# 12_LMS2_Power.net
KiCad netlist of a schematic drawn in Altium Designer
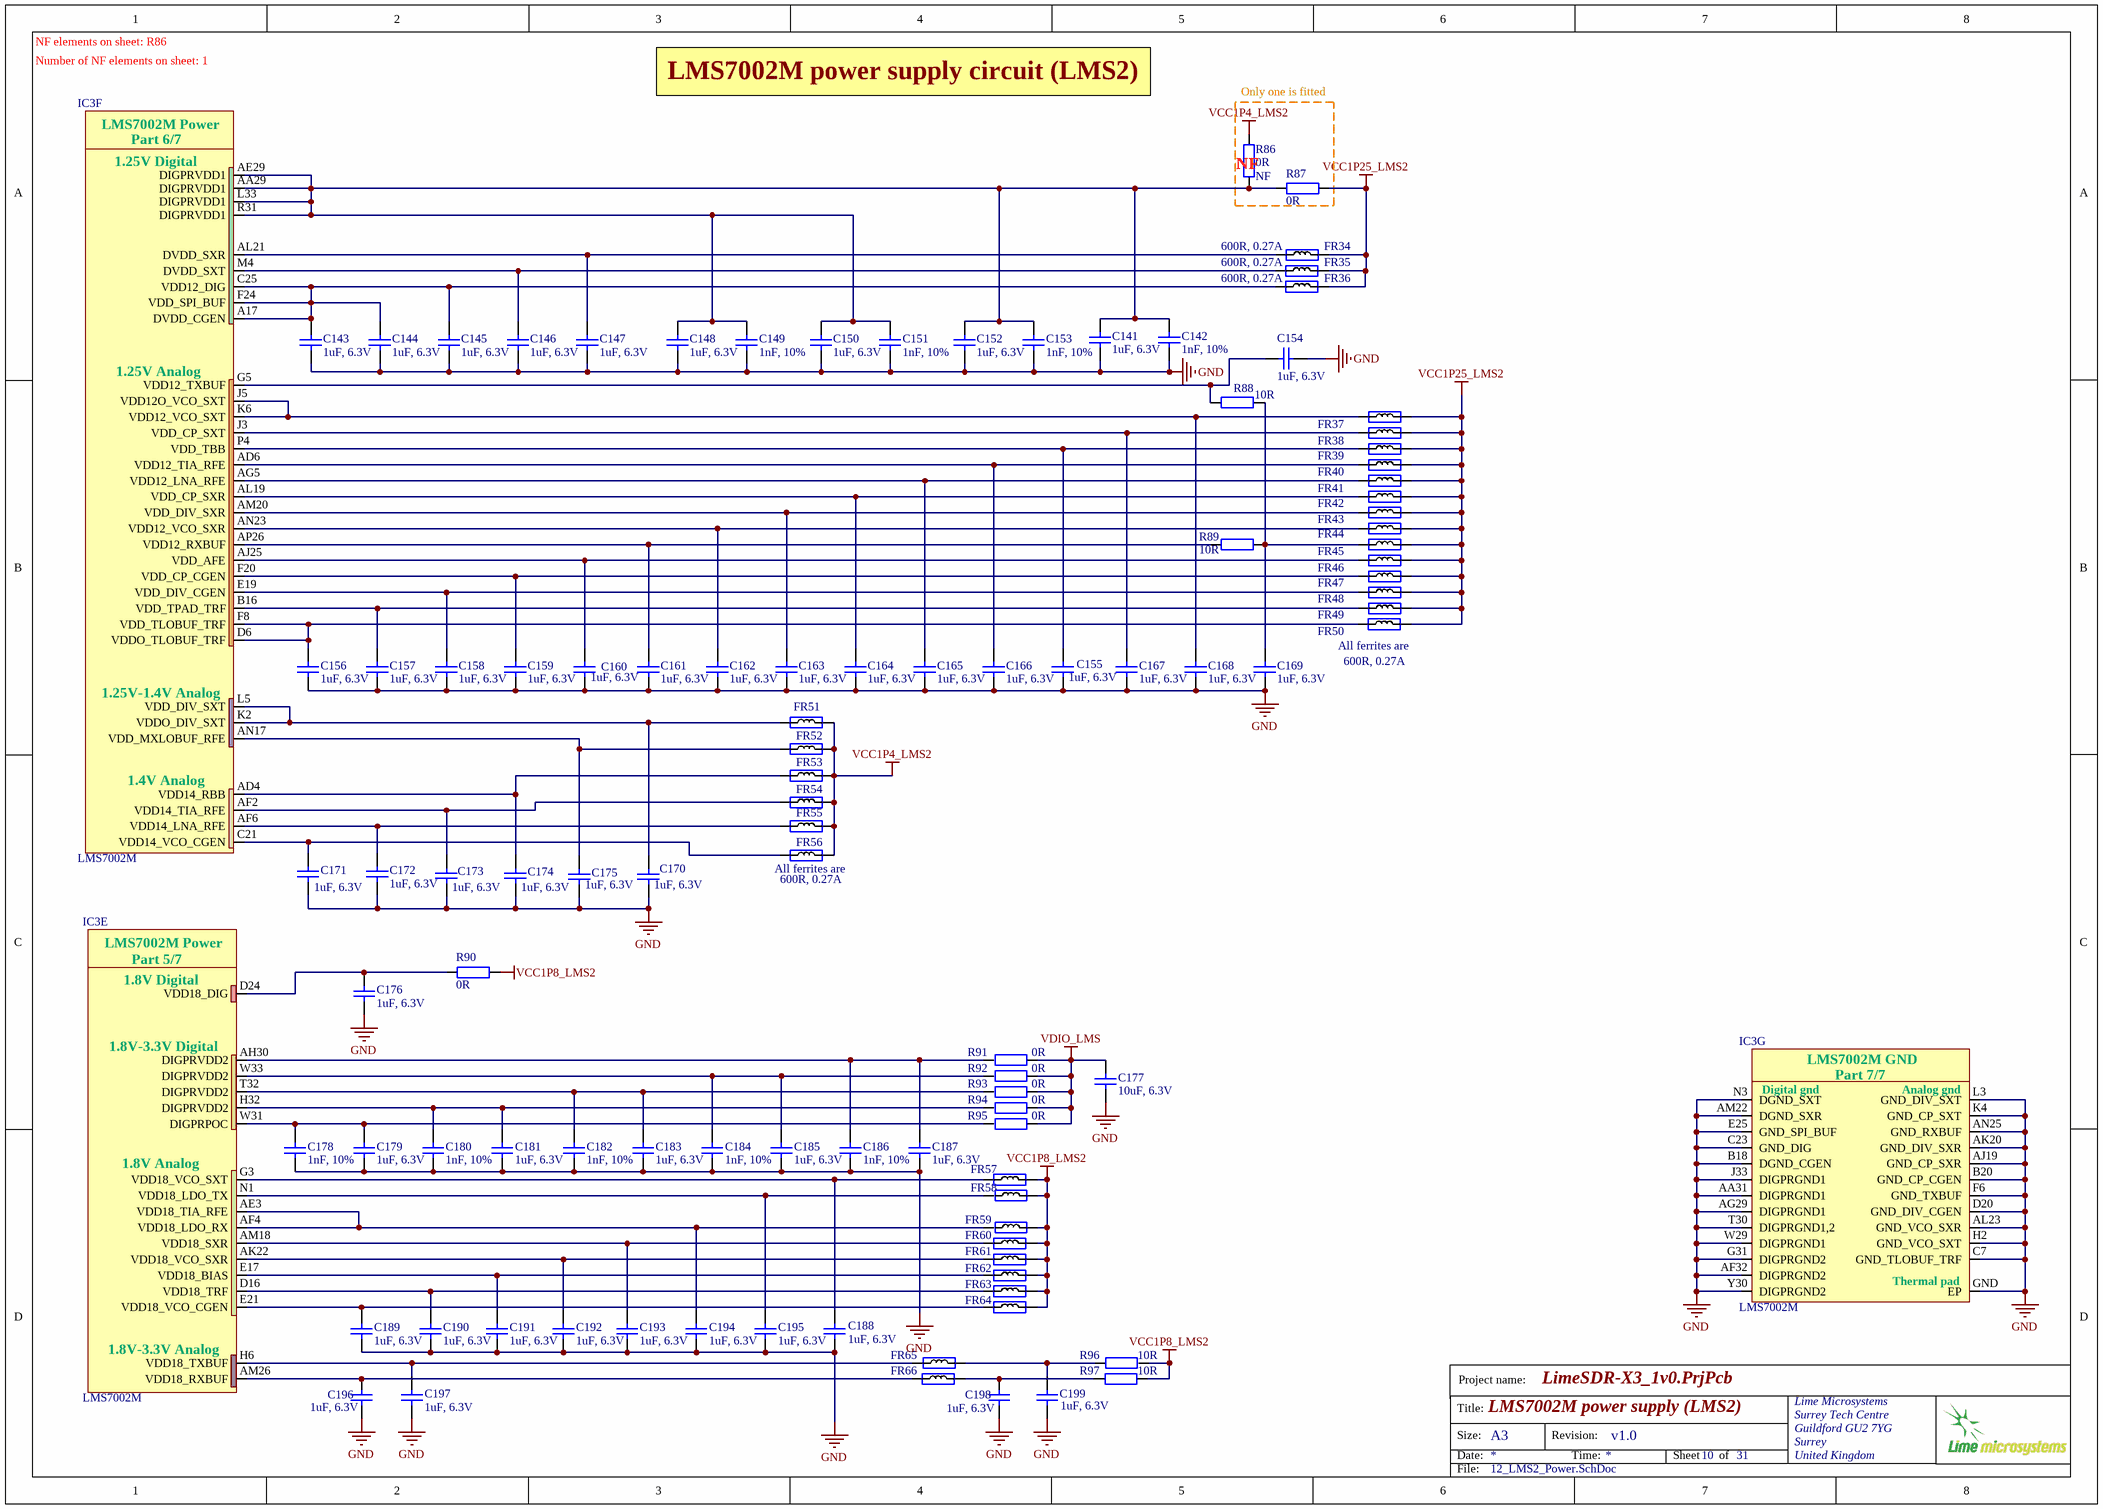
[diagram p0: 12_LMS2_Power.SchDoc]

(export (version "E")
  (design (tool "Eeschema 10.0.6"))
  (components
    (comp (ref "C141")
      (value "1uF, 6.3V")
      (footprint "CAP0201")
      (fields (field (name "TOLERANCE") "±20%") (field (name "MANUFACTURER") "TDK Corporation"))
      (libsource (lib "") (part "Cap_0402_2"))
    )
    (comp (ref "C142")
      (value "1nF, 10%")
      (footprint "CAP0201")
      (fields (field (name "TOLERANCE") "±10%") (field (name "MANUFACTURER") "TDK Corporation"))
      (libsource (lib "") (part "Cap_0402_2"))
    )
    (comp (ref "C143")
      (value "1uF, 6.3V")
      (footprint "CAP0201")
      (fields (field (name "TOLERANCE") "±20%") (field (name "MANUFACTURER") "TDK Corporation"))
      (libsource (lib "") (part "Cap_0402_1"))
    )
    (comp (ref "C144")
      (value "1uF, 6.3V")
      (footprint "CAP0201")
      (fields (field (name "TOLERANCE") "±20%") (field (name "MANUFACTURER") "TDK Corporation"))
      (libsource (lib "") (part "Cap_0402_1"))
    )
    (comp (ref "C145")
      (value "1uF, 6.3V")
      (footprint "CAP0201")
      (fields (field (name "TOLERANCE") "±20%") (field (name "MANUFACTURER") "TDK Corporation"))
      (libsource (lib "") (part "Cap_0402_1"))
    )
    (comp (ref "C146")
      (value "1uF, 6.3V")
      (footprint "CAP0201")
      (fields (field (name "TOLERANCE") "±20%") (field (name "MANUFACTURER") "TDK Corporation"))
      (libsource (lib "") (part "Cap_0402_2"))
    )
    (comp (ref "C147")
      (value "1uF, 6.3V")
      (footprint "CAP0201")
      (fields (field (name "TOLERANCE") "±20%") (field (name "MANUFACTURER") "TDK Corporation"))
      (libsource (lib "") (part "Cap_0402_1"))
    )
    (comp (ref "C148")
      (value "1uF, 6.3V")
      (footprint "CAP0201")
      (fields (field (name "TOLERANCE") "±20%") (field (name "MANUFACTURER") "TDK Corporation"))
      (libsource (lib "") (part "Cap_0402_2"))
    )
    (comp (ref "C149")
      (value "1nF, 10%")
      (footprint "CAP0201")
      (fields (field (name "TOLERANCE") "±10%") (field (name "MANUFACTURER") "TDK Corporation"))
      (libsource (lib "") (part "Cap_0402_2"))
    )
    (comp (ref "C150")
      (value "1uF, 6.3V")
      (footprint "CAP0201")
      (fields (field (name "TOLERANCE") "±20%") (field (name "MANUFACTURER") "TDK Corporation"))
      (libsource (lib "") (part "Cap_0402_2"))
    )
    (comp (ref "C151")
      (value "1nF, 10%")
      (footprint "CAP0201")
      (fields (field (name "TOLERANCE") "±10%") (field (name "MANUFACTURER") "TDK Corporation"))
      (libsource (lib "") (part "Cap_0402_2"))
    )
    (comp (ref "C152")
      (value "1uF, 6.3V")
      (footprint "CAP0201")
      (fields (field (name "TOLERANCE") "±20%") (field (name "MANUFACTURER") "TDK Corporation"))
      (libsource (lib "") (part "Cap_0402_2"))
    )
    (comp (ref "C153")
      (value "1nF, 10%")
      (footprint "CAP0201")
      (fields (field (name "TOLERANCE") "±10%") (field (name "MANUFACTURER") "TDK Corporation"))
      (libsource (lib "") (part "Cap_0402_2"))
    )
    (comp (ref "C154")
      (value "1uF, 6.3V")
      (footprint "CAP0201")
      (fields (field (name "TOLERANCE") "±20%") (field (name "MANUFACTURER") "TDK Corporation"))
      (libsource (lib "") (part "Cap_0402_4"))
    )
    (comp (ref "C155")
      (value "1uF, 6.3V")
      (footprint "CAP0201")
      (fields (field (name "TOLERANCE") "±20%") (field (name "MANUFACTURER") "TDK Corporation"))
      (libsource (lib "") (part "Cap_0402_1"))
    )
    (comp (ref "C156")
      (value "1uF, 6.3V")
      (footprint "CAP0201")
      (fields (field (name "TOLERANCE") "±20%") (field (name "MANUFACTURER") "TDK Corporation"))
      (libsource (lib "") (part "Cap_0402_1"))
    )
    (comp (ref "C157")
      (value "1uF, 6.3V")
      (footprint "CAP0201")
      (fields (field (name "TOLERANCE") "±20%") (field (name "MANUFACTURER") "TDK Corporation"))
      (libsource (lib "") (part "Cap_0402_1"))
    )
    (comp (ref "C158")
      (value "1uF, 6.3V")
      (footprint "CAP0201")
      (fields (field (name "TOLERANCE") "±20%") (field (name "MANUFACTURER") "TDK Corporation"))
      (libsource (lib "") (part "Cap_0402_1"))
    )
    (comp (ref "C159")
      (value "1uF, 6.3V")
      (footprint "CAP0201")
      (fields (field (name "TOLERANCE") "±20%") (field (name "MANUFACTURER") "TDK Corporation"))
      (libsource (lib "") (part "Cap_0402_2"))
    )
    (comp (ref "C160")
      (value "1uF, 6.3V")
      (footprint "CAP0201")
      (fields (field (name "TOLERANCE") "±20%") (field (name "MANUFACTURER") "TDK Corporation"))
      (libsource (lib "") (part "Cap_0402_1"))
    )
    (comp (ref "C161")
      (value "1uF, 6.3V")
      (footprint "CAP0201")
      (fields (field (name "TOLERANCE") "±20%") (field (name "MANUFACTURER") "TDK Corporation"))
      (libsource (lib "") (part "Cap_0402_1"))
    )
    (comp (ref "C162")
      (value "1uF, 6.3V")
      (footprint "CAP0201")
      (fields (field (name "TOLERANCE") "±20%") (field (name "MANUFACTURER") "TDK Corporation"))
      (libsource (lib "") (part "Cap_0402_1"))
    )
    (comp (ref "C163")
      (value "1uF, 6.3V")
      (footprint "CAP0201")
      (fields (field (name "TOLERANCE") "±20%") (field (name "MANUFACTURER") "TDK Corporation"))
      (libsource (lib "") (part "Cap_0402_1"))
    )
    (comp (ref "C164")
      (value "1uF, 6.3V")
      (footprint "CAP0201")
      (fields (field (name "TOLERANCE") "±20%") (field (name "MANUFACTURER") "TDK Corporation"))
      (libsource (lib "") (part "Cap_0402_1"))
    )
    (comp (ref "C165")
      (value "1uF, 6.3V")
      (footprint "CAP0201")
      (fields (field (name "TOLERANCE") "±20%") (field (name "MANUFACTURER") "TDK Corporation"))
      (libsource (lib "") (part "Cap_0402_1"))
    )
    (comp (ref "C166")
      (value "1uF, 6.3V")
      (footprint "CAP0201")
      (fields (field (name "TOLERANCE") "±20%") (field (name "MANUFACTURER") "TDK Corporation"))
      (libsource (lib "") (part "Cap_0402_2"))
    )
    (comp (ref "C167")
      (value "1uF, 6.3V")
      (footprint "CAP0201")
      (fields (field (name "TOLERANCE") "±20%") (field (name "MANUFACTURER") "TDK Corporation"))
      (libsource (lib "") (part "Cap_0402_1"))
    )
    (comp (ref "C168")
      (value "1uF, 6.3V")
      (footprint "CAP0201")
      (fields (field (name "TOLERANCE") "±20%") (field (name "MANUFACTURER") "TDK Corporation"))
      (libsource (lib "") (part "Cap_0402_2"))
    )
    (comp (ref "C169")
      (value "1uF, 6.3V")
      (footprint "CAP0201")
      (fields (field (name "TOLERANCE") "±20%") (field (name "MANUFACTURER") "TDK Corporation"))
      (libsource (lib "") (part "Cap_0402_2"))
    )
    (comp (ref "C170")
      (value "1uF, 6.3V")
      (footprint "CAP0201")
      (fields (field (name "TOLERANCE") "±20%") (field (name "MANUFACTURER") "TDK Corporation"))
      (libsource (lib "") (part "Cap_0402_1"))
    )
    (comp (ref "C171")
      (value "1uF, 6.3V")
      (footprint "CAP0201")
      (fields (field (name "TOLERANCE") "±20%") (field (name "MANUFACTURER") "TDK Corporation"))
      (libsource (lib "") (part "Cap_0402_1"))
    )
    (comp (ref "C172")
      (value "1uF, 6.3V")
      (footprint "CAP0201")
      (fields (field (name "TOLERANCE") "±20%") (field (name "MANUFACTURER") "TDK Corporation"))
      (libsource (lib "") (part "Cap_0402_1"))
    )
    (comp (ref "C173")
      (value "1uF, 6.3V")
      (footprint "CAP0201")
      (fields (field (name "TOLERANCE") "±20%") (field (name "MANUFACTURER") "TDK Corporation"))
      (libsource (lib "") (part "Cap_0402_3"))
    )
    (comp (ref "C174")
      (value "1uF, 6.3V")
      (footprint "CAP0201")
      (fields (field (name "TOLERANCE") "±20%") (field (name "MANUFACTURER") "TDK Corporation"))
      (libsource (lib "") (part "Cap_0402_3"))
    )
    (comp (ref "C175")
      (value "1uF, 6.3V")
      (footprint "CAP0201")
      (fields (field (name "TOLERANCE") "±20%") (field (name "MANUFACTURER") "TDK Corporation"))
      (libsource (lib "") (part "Cap_0402_1"))
    )
    (comp (ref "C176")
      (value "1uF, 6.3V")
      (footprint "CAP0201")
      (fields (field (name "TOLERANCE") "±20%") (field (name "MANUFACTURER") "TDK Corporation"))
      (libsource (lib "LimeMicroAltiumLib_schLib") (part "Cap_0402"))
    )
    (comp (ref "C177")
      (value "10uF, 6.3V")
      (footprint "CAP0603")
      (fields (field (name "TOLERANCE") "±20%") (field (name "MANUFACTURER") "Yageo"))
      (libsource (lib "LimeFPGAboard_schLib") (part "Cap_0603"))
    )
    (comp (ref "C178")
      (value "1nF, 10%")
      (footprint "CAP0201")
      (fields (field (name "TOLERANCE") "±10%") (field (name "MANUFACTURER") "TDK Corporation"))
      (libsource (lib "LimeMicroAltiumLib_schLib") (part "Cap_0402"))
    )
    (comp (ref "C179")
      (value "1uF, 6.3V")
      (footprint "CAP0201")
      (fields (field (name "TOLERANCE") "±20%") (field (name "MANUFACTURER") "TDK Corporation"))
      (libsource (lib "LimeMicroAltiumLib_schLib") (part "Cap_0402"))
    )
    (comp (ref "C180")
      (value "1nF, 10%")
      (footprint "CAP0201")
      (fields (field (name "TOLERANCE") "±10%") (field (name "MANUFACTURER") "TDK Corporation"))
      (libsource (lib "LimeMicroAltiumLib_schLib") (part "Cap_0402"))
    )
    (comp (ref "C181")
      (value "1uF, 6.3V")
      (footprint "CAP0201")
      (fields (field (name "TOLERANCE") "±20%") (field (name "MANUFACTURER") "TDK Corporation"))
      (libsource (lib "LimeMicroAltiumLib_schLib") (part "Cap_0402"))
    )
    (comp (ref "C182")
      (value "1nF, 10%")
      (footprint "CAP0201")
      (fields (field (name "TOLERANCE") "±10%") (field (name "MANUFACTURER") "TDK Corporation"))
      (libsource (lib "LimeMicroAltiumLib_schLib") (part "Cap_0402"))
    )
    (comp (ref "C183")
      (value "1uF, 6.3V")
      (footprint "CAP0201")
      (fields (field (name "TOLERANCE") "±20%") (field (name "MANUFACTURER") "TDK Corporation"))
      (libsource (lib "LimeMicroAltiumLib_schLib") (part "Cap_0402"))
    )
    (comp (ref "C184")
      (value "1nF, 10%")
      (footprint "CAP0201")
      (fields (field (name "TOLERANCE") "±10%") (field (name "MANUFACTURER") "TDK Corporation"))
      (libsource (lib "LimeMicroAltiumLib_schLib") (part "Cap_0402"))
    )
    (comp (ref "C185")
      (value "1uF, 6.3V")
      (footprint "CAP0201")
      (fields (field (name "TOLERANCE") "±20%") (field (name "MANUFACTURER") "TDK Corporation"))
      (libsource (lib "LimeMicroAltiumLib_schLib") (part "Cap_0402"))
    )
    (comp (ref "C186")
      (value "1nF, 10%")
      (footprint "CAP0201")
      (fields (field (name "TOLERANCE") "±10%") (field (name "MANUFACTURER") "TDK Corporation"))
      (libsource (lib "LimeMicroAltiumLib_schLib") (part "Cap_0402"))
    )
    (comp (ref "C187")
      (value "1uF, 6.3V")
      (footprint "CAP0201")
      (fields (field (name "TOLERANCE") "±20%") (field (name "MANUFACTURER") "TDK Corporation"))
      (libsource (lib "LimeMicroAltiumLib_schLib") (part "Cap_0402"))
    )
    (comp (ref "C188")
      (value "1uF, 6.3V")
      (footprint "CAP0201")
      (fields (field (name "TOLERANCE") "±20%") (field (name "MANUFACTURER") "TDK Corporation"))
      (libsource (lib "LimeMicroAltiumLib_schLib") (part "Cap_0402"))
    )
    (comp (ref "C189")
      (value "1uF, 6.3V")
      (footprint "CAP0201")
      (fields (field (name "TOLERANCE") "±20%") (field (name "MANUFACTURER") "TDK Corporation"))
      (libsource (lib "LimeMicroAltiumLib_schLib") (part "Cap_0402"))
    )
    (comp (ref "C190")
      (value "1uF, 6.3V")
      (footprint "CAP0201")
      (fields (field (name "TOLERANCE") "±20%") (field (name "MANUFACTURER") "TDK Corporation"))
      (libsource (lib "LimeMicroAltiumLib_schLib") (part "Cap_0402"))
    )
    (comp (ref "C191")
      (value "1uF, 6.3V")
      (footprint "CAP0201")
      (fields (field (name "TOLERANCE") "±20%") (field (name "MANUFACTURER") "TDK Corporation"))
      (libsource (lib "LimeMicroAltiumLib_schLib") (part "Cap_0402"))
    )
    (comp (ref "C192")
      (value "1uF, 6.3V")
      (footprint "CAP0201")
      (fields (field (name "TOLERANCE") "±20%") (field (name "MANUFACTURER") "TDK Corporation"))
      (libsource (lib "LimeMicroAltiumLib_schLib") (part "Cap_0402"))
    )
    (comp (ref "C193")
      (value "1uF, 6.3V")
      (footprint "CAP0201")
      (fields (field (name "TOLERANCE") "±20%") (field (name "MANUFACTURER") "TDK Corporation"))
      (libsource (lib "LimeMicroAltiumLib_schLib") (part "Cap_0402"))
    )
    (comp (ref "C194")
      (value "1uF, 6.3V")
      (footprint "CAP0201")
      (fields (field (name "TOLERANCE") "±20%") (field (name "MANUFACTURER") "TDK Corporation"))
      (libsource (lib "LimeMicroAltiumLib_schLib") (part "Cap_0402"))
    )
    (comp (ref "C195")
      (value "1uF, 6.3V")
      (footprint "CAP0201")
      (fields (field (name "TOLERANCE") "±20%") (field (name "MANUFACTURER") "TDK Corporation"))
      (libsource (lib "LimeMicroAltiumLib_schLib") (part "Cap_0402"))
    )
    (comp (ref "C196")
      (value "1uF, 6.3V")
      (footprint "CAP0201")
      (fields (field (name "TOLERANCE") "±20%") (field (name "MANUFACTURER") "TDK Corporation"))
      (libsource (lib "LimeMicroAltiumLib_schLib") (part "Cap_0402"))
    )
    (comp (ref "C197")
      (value "1uF, 6.3V")
      (footprint "CAP0201")
      (fields (field (name "TOLERANCE") "±20%") (field (name "MANUFACTURER") "TDK Corporation"))
      (libsource (lib "LimeMicroAltiumLib_schLib") (part "Cap_0402"))
    )
    (comp (ref "C198")
      (value "1uF, 6.3V")
      (footprint "CAP0201")
      (fields (field (name "TOLERANCE") "±20%") (field (name "MANUFACTURER") "TDK Corporation"))
      (libsource (lib "LimeMicroAltiumLib_schLib") (part "Cap_0402"))
    )
    (comp (ref "C199")
      (value "1uF, 6.3V")
      (footprint "CAP0201")
      (fields (field (name "TOLERANCE") "±20%") (field (name "MANUFACTURER") "TDK Corporation"))
      (libsource (lib "LimeMicroAltiumLib_schLib") (part "Cap_0402"))
    )
    (comp (ref "FR34")
      (value "600R, 0.27A")
      (footprint "RES0201")
      (fields (field (name "MANUFACTURER") "Taiyo Yuden"))
      (libsource (lib "") (part "Ferrite_2"))
    )
    (comp (ref "FR35")
      (value "600R, 0.27A")
      (footprint "RES0201")
      (fields (field (name "MANUFACTURER") "Taiyo Yuden"))
      (libsource (lib "") (part "Ferrite_1"))
    )
    (comp (ref "FR36")
      (value "600R, 0.27A")
      (footprint "RES0201")
      (fields (field (name "MANUFACTURER") "Taiyo Yuden"))
      (libsource (lib "") (part "Ferrite_1"))
    )
    (comp (ref "FR37")
      (value "600R, 0.27A")
      (footprint "RES0201")
      (fields (field (name "MANUFACTURER") "Taiyo Yuden"))
      (libsource (lib "") (part "Ferrite_2"))
    )
    (comp (ref "FR38")
      (value "600R, 0.27A")
      (footprint "RES0201")
      (fields (field (name "MANUFACTURER") "Taiyo Yuden"))
      (libsource (lib "") (part "Ferrite_2"))
    )
    (comp (ref "FR39")
      (value "600R, 0.27A")
      (footprint "RES0201")
      (fields (field (name "MANUFACTURER") "Taiyo Yuden"))
      (libsource (lib "") (part "Ferrite_2"))
    )
    (comp (ref "FR40")
      (value "600R, 0.27A")
      (footprint "RES0201")
      (fields (field (name "MANUFACTURER") "Taiyo Yuden"))
      (libsource (lib "") (part "Ferrite_2"))
    )
    (comp (ref "FR41")
      (value "600R, 0.27A")
      (footprint "RES0201")
      (fields (field (name "MANUFACTURER") "Taiyo Yuden"))
      (libsource (lib "") (part "Ferrite_2"))
    )
    (comp (ref "FR42")
      (value "600R, 0.27A")
      (footprint "RES0201")
      (fields (field (name "MANUFACTURER") "Taiyo Yuden"))
      (libsource (lib "") (part "Ferrite_2"))
    )
    (comp (ref "FR43")
      (value "600R, 0.27A")
      (footprint "RES0201")
      (fields (field (name "MANUFACTURER") "Taiyo Yuden"))
      (libsource (lib "") (part "Ferrite_2"))
    )
    (comp (ref "FR44")
      (value "600R, 0.27A")
      (footprint "RES0201")
      (fields (field (name "MANUFACTURER") "Taiyo Yuden"))
      (libsource (lib "") (part "Ferrite_2"))
    )
    (comp (ref "FR45")
      (value "600R, 0.27A")
      (footprint "RES0201")
      (fields (field (name "MANUFACTURER") "Taiyo Yuden"))
      (libsource (lib "") (part "Ferrite_2"))
    )
    (comp (ref "FR46")
      (value "600R, 0.27A")
      (footprint "RES0201")
      (fields (field (name "MANUFACTURER") "Taiyo Yuden"))
      (libsource (lib "") (part "Ferrite_2"))
    )
    (comp (ref "FR47")
      (value "600R, 0.27A")
      (footprint "RES0201")
      (fields (field (name "MANUFACTURER") "Taiyo Yuden"))
      (libsource (lib "") (part "Ferrite_2"))
    )
    (comp (ref "FR48")
      (value "600R, 0.27A")
      (footprint "RES0201")
      (fields (field (name "MANUFACTURER") "Taiyo Yuden"))
      (libsource (lib "") (part "Ferrite_2"))
    )
    (comp (ref "FR49")
      (value "600R, 0.27A")
      (footprint "RES0201")
      (fields (field (name "MANUFACTURER") "Taiyo Yuden"))
      (libsource (lib "") (part "Ferrite_2"))
    )
    (comp (ref "FR50")
      (value "600R, 0.27A")
      (footprint "RES0201")
      (fields (field (name "MANUFACTURER") "Taiyo Yuden"))
      (libsource (lib "") (part "Ferrite_1"))
    )
    (comp (ref "FR51")
      (value "600R, 0.27A")
      (footprint "RES0201")
      (fields (field (name "MANUFACTURER") "Taiyo Yuden"))
      (libsource (lib "") (part "Ferrite_1"))
    )
    (comp (ref "FR52")
      (value "600R, 0.27A")
      (footprint "RES0201")
      (fields (field (name "MANUFACTURER") "Taiyo Yuden"))
      (libsource (lib "") (part "Ferrite_1"))
    )
    (comp (ref "FR53")
      (value "600R, 0.27A")
      (footprint "RES0201")
      (fields (field (name "MANUFACTURER") "Taiyo Yuden"))
      (libsource (lib "") (part "Ferrite_1"))
    )
    (comp (ref "FR54")
      (value "600R, 0.27A")
      (footprint "RES0201")
      (fields (field (name "MANUFACTURER") "Taiyo Yuden"))
      (libsource (lib "") (part "Ferrite_1"))
    )
    (comp (ref "FR55")
      (value "600R, 0.27A")
      (footprint "RES0201")
      (fields (field (name "MANUFACTURER") "Taiyo Yuden"))
      (libsource (lib "") (part "Ferrite_1"))
    )
    (comp (ref "FR56")
      (value "600R, 0.27A")
      (footprint "RES0201")
      (fields (field (name "MANUFACTURER") "Taiyo Yuden"))
      (libsource (lib "") (part "Ferrite_1"))
    )
    (comp (ref "FR57")
      (value "600R, 0.27A")
      (footprint "RES0201")
      (fields (field (name "MANUFACTURER") "Taiyo Yuden"))
      (libsource (lib "") (part "Ferrite_1"))
    )
    (comp (ref "FR58")
      (value "600R, 0.27A")
      (footprint "RES0201")
      (fields (field (name "MANUFACTURER") "Taiyo Yuden"))
      (libsource (lib "LimeMicroAltiumLib_schLib") (part "Ferrite"))
    )
    (comp (ref "FR59")
      (value "600R, 0.27A")
      (footprint "RES0201")
      (fields (field (name "MANUFACTURER") "Taiyo Yuden"))
      (libsource (lib "LimeMicroAltiumLib_schLib") (part "Ferrite"))
    )
    (comp (ref "FR60")
      (value "600R, 0.27A")
      (footprint "RES0201")
      (fields (field (name "MANUFACTURER") "Taiyo Yuden"))
      (libsource (lib "") (part "Ferrite_1"))
    )
    (comp (ref "FR61")
      (value "600R, 0.27A")
      (footprint "RES0201")
      (fields (field (name "MANUFACTURER") "Taiyo Yuden"))
      (libsource (lib "") (part "Ferrite_1"))
    )
    (comp (ref "FR62")
      (value "600R, 0.27A")
      (footprint "RES0201")
      (fields (field (name "MANUFACTURER") "Taiyo Yuden"))
      (libsource (lib "") (part "Ferrite_1"))
    )
    (comp (ref "FR63")
      (value "600R, 0.27A")
      (footprint "RES0201")
      (fields (field (name "MANUFACTURER") "Taiyo Yuden"))
      (libsource (lib "") (part "Ferrite_1"))
    )
    (comp (ref "FR64")
      (value "600R, 0.27A")
      (footprint "RES0201")
      (fields (field (name "MANUFACTURER") "Taiyo Yuden"))
      (libsource (lib "") (part "Ferrite_1"))
    )
    (comp (ref "FR65")
      (value "600R, 0.27A")
      (footprint "RES0201")
      (fields (field (name "MANUFACTURER") "Taiyo Yuden"))
      (libsource (lib "LimeMicroAltiumLib_schLib") (part "Ferrite"))
    )
    (comp (ref "FR66")
      (value "600R, 0.27A")
      (footprint "RES0201")
      (fields (field (name "MANUFACTURER") "Taiyo Yuden"))
      (libsource (lib "") (part "Ferrite_1"))
    )
    (comp (ref "IC3")
      (value "LMS7002M")
      (footprint "LMS7002M_v5")
      (description "Schematic symbol revision 4. Default footprint - 0.31mm pad")
      (fields (field (name "MANUFACTURER") "Lime Microsystems"))
      (libsource (lib "LimeMicroAltiumLib_schLib_r04") (part "LMS7002Mr4"))
    )
    (comp (ref "R86")
      (value "0R")
      (footprint "RES0402")
      (fields
        (field (name "ASSEMBLY INFO") "NF")
        (field (name "MANUFACTURER") "Yageo")
        (field (name "TOLERANCE") "Jumper")
      )
      (libsource (lib "LimeMicroAltiumLib_schLib") (part "Res_0402"))
    )
    (comp (ref "R87")
      (value "0R")
      (footprint "RES0402")
      (fields (field (name "MANUFACTURER") "Yageo") (field (name "TOLERANCE") "Jumper"))
      (libsource (lib "") (part "Res_0402_1"))
    )
    (comp (ref "R88")
      (value "10R")
      (footprint "RES0201")
      (fields
        (field (name "MANUFACTURER") "Panasonic Electronic Components")
        (field (name "TOLERANCE") "±1%")
      )
      (libsource (lib "LimeMicroAltiumLib_schLib") (part "Res_0402"))
    )
    (comp (ref "R89")
      (value "10R")
      (footprint "RES0201")
      (fields
        (field (name "MANUFACTURER") "Panasonic Electronic Components")
        (field (name "TOLERANCE") "±1%")
      )
      (libsource (lib "LimeMicroAltiumLib_schLib") (part "Res_0402"))
    )
    (comp (ref "R90")
      (value "0R")
      (footprint "RES0201")
      (fields (field (name "MANUFACTURER") "Rohm Semiconductor") (field (name "TOLERANCE") "Jumper"))
      (libsource (lib "LimeMicroAltiumLib_schLib") (part "Res_0402"))
    )
    (comp (ref "R91")
      (value "0R")
      (footprint "RES0402")
      (fields (field (name "MANUFACTURER") "Yageo") (field (name "TOLERANCE") "Jumper"))
      (libsource (lib "LimeMicroAltiumLib_schLib") (part "Res_0402"))
    )
    (comp (ref "R92")
      (value "0R")
      (footprint "RES0402")
      (fields (field (name "MANUFACTURER") "Yageo") (field (name "TOLERANCE") "Jumper"))
      (libsource (lib "LimeMicroAltiumLib_schLib") (part "Res_0402"))
    )
    (comp (ref "R93")
      (value "0R")
      (footprint "RES0402")
      (fields (field (name "MANUFACTURER") "Yageo") (field (name "TOLERANCE") "Jumper"))
      (libsource (lib "LimeMicroAltiumLib_schLib") (part "Res_0402"))
    )
    (comp (ref "R94")
      (value "0R")
      (footprint "RES0402")
      (fields (field (name "MANUFACTURER") "Yageo") (field (name "TOLERANCE") "Jumper"))
      (libsource (lib "LimeMicroAltiumLib_schLib") (part "Res_0402"))
    )
    (comp (ref "R95")
      (value "0R")
      (footprint "RES0402")
      (fields (field (name "MANUFACTURER") "Yageo") (field (name "TOLERANCE") "Jumper"))
      (libsource (lib "LimeMicroAltiumLib_schLib") (part "Res_0402"))
    )
    (comp (ref "R96")
      (value "10R")
      (footprint "RES0201")
      (fields
        (field (name "MANUFACTURER") "Panasonic Electronic Components")
        (field (name "TOLERANCE") "±1%")
      )
      (libsource (lib "LimeMicroAltiumLib_schLib") (part "Res_0402"))
    )
    (comp (ref "R97")
      (value "10R")
      (footprint "RES0201")
      (fields
        (field (name "MANUFACTURER") "Panasonic Electronic Components")
        (field (name "TOLERANCE") "±1%")
      )
      (libsource (lib "LimeMicroAltiumLib_schLib") (part "Res_0402"))
    )
  )
  (nets
    (net (code "1") (name "GND") (class "Default")
      (node (ref "C141") (pin "2") (pinfunction "2_2") (pintype "passive"))
      (node (ref "C142") (pin "2") (pinfunction "2_2") (pintype "passive"))
      (node (ref "C143") (pin "2") (pinfunction "2_2") (pintype "passive"))
      (node (ref "C144") (pin "2") (pinfunction "2_2") (pintype "passive"))
      (node (ref "C145") (pin "2") (pinfunction "2_2") (pintype "passive"))
      (node (ref "C146") (pin "1") (pinfunction "1_1") (pintype "passive"))
      (node (ref "C147") (pin "2") (pinfunction "2_2") (pintype "passive"))
      (node (ref "C148") (pin "2") (pinfunction "2_2") (pintype "passive"))
      (node (ref "C149") (pin "2") (pinfunction "2_2") (pintype "passive"))
      (node (ref "C150") (pin "2") (pinfunction "2_2") (pintype "passive"))
      (node (ref "C151") (pin "2") (pinfunction "2_2") (pintype "passive"))
      (node (ref "C152") (pin "2") (pinfunction "2_2") (pintype "passive"))
      (node (ref "C153") (pin "2") (pinfunction "2_2") (pintype "passive"))
      (node (ref "C154") (pin "2") (pinfunction "2_2") (pintype "passive"))
      (node (ref "C155") (pin "2") (pinfunction "2_2") (pintype "passive"))
      (node (ref "C156") (pin "2") (pinfunction "2_2") (pintype "passive"))
      (node (ref "C157") (pin "2") (pinfunction "2_2") (pintype "passive"))
      (node (ref "C158") (pin "2") (pinfunction "2_2") (pintype "passive"))
      (node (ref "C159") (pin "1") (pinfunction "1_1") (pintype "passive"))
      (node (ref "C160") (pin "2") (pinfunction "2_2") (pintype "passive"))
      (node (ref "C161") (pin "2") (pinfunction "2_2") (pintype "passive"))
      (node (ref "C162") (pin "2") (pinfunction "2_2") (pintype "passive"))
      (node (ref "C163") (pin "2") (pinfunction "2_2") (pintype "passive"))
      (node (ref "C164") (pin "2") (pinfunction "2_2") (pintype "passive"))
      (node (ref "C165") (pin "2") (pinfunction "2_2") (pintype "passive"))
      (node (ref "C166") (pin "1") (pinfunction "1_1") (pintype "passive"))
      (node (ref "C167") (pin "2") (pinfunction "2_2") (pintype "passive"))
      (node (ref "C168") (pin "1") (pinfunction "1_1") (pintype "passive"))
      (node (ref "C169") (pin "1") (pinfunction "1_1") (pintype "passive"))
      (node (ref "C170") (pin "2") (pinfunction "2_2") (pintype "passive"))
      (node (ref "C171") (pin "2") (pinfunction "2_2") (pintype "passive"))
      (node (ref "C172") (pin "2") (pinfunction "2_2") (pintype "passive"))
      (node (ref "C173") (pin "2") (pinfunction "2_2") (pintype "passive"))
      (node (ref "C174") (pin "2") (pinfunction "2_2") (pintype "passive"))
      (node (ref "C175") (pin "2") (pinfunction "2_2") (pintype "passive"))
      (node (ref "C176") (pin "2") (pinfunction "2_2") (pintype "passive"))
      (node (ref "C177") (pin "1") (pinfunction "1_1") (pintype "passive"))
      (node (ref "C178") (pin "2") (pinfunction "2_2") (pintype "passive"))
      (node (ref "C179") (pin "2") (pinfunction "2_2") (pintype "passive"))
      (node (ref "C180") (pin "2") (pinfunction "2_2") (pintype "passive"))
      (node (ref "C181") (pin "2") (pinfunction "2_2") (pintype "passive"))
      (node (ref "C182") (pin "2") (pinfunction "2_2") (pintype "passive"))
      (node (ref "C183") (pin "2") (pinfunction "2_2") (pintype "passive"))
      (node (ref "C184") (pin "2") (pinfunction "2_2") (pintype "passive"))
      (node (ref "C185") (pin "2") (pinfunction "2_2") (pintype "passive"))
      (node (ref "C186") (pin "2") (pinfunction "2_2") (pintype "passive"))
      (node (ref "C187") (pin "2") (pinfunction "2_2") (pintype "passive"))
      (node (ref "C188") (pin "2") (pinfunction "2_2") (pintype "passive"))
      (node (ref "C189") (pin "2") (pinfunction "2_2") (pintype "passive"))
      (node (ref "C190") (pin "2") (pinfunction "2_2") (pintype "passive"))
      (node (ref "C191") (pin "2") (pinfunction "2_2") (pintype "passive"))
      (node (ref "C192") (pin "2") (pinfunction "2_2") (pintype "passive"))
      (node (ref "C193") (pin "2") (pinfunction "2_2") (pintype "passive"))
      (node (ref "C194") (pin "2") (pinfunction "2_2") (pintype "passive"))
      (node (ref "C195") (pin "2") (pinfunction "2_2") (pintype "passive"))
      (node (ref "C196") (pin "2") (pinfunction "2_2") (pintype "passive"))
      (node (ref "C197") (pin "2") (pinfunction "2_2") (pintype "passive"))
      (node (ref "C198") (pin "2") (pinfunction "2_2") (pintype "passive"))
      (node (ref "C199") (pin "2") (pinfunction "2_2") (pintype "passive"))
      (node (ref "IC3") (pin "AA31") (pinfunction "DIGPRGND1_AA31") (pintype "passive"))
      (node (ref "IC3") (pin "AF32") (pinfunction "DIGPRGND2_AF32") (pintype "passive"))
      (node (ref "IC3") (pin "AG29") (pinfunction "DIGPRGND1_AG29") (pintype "passive"))
      (node (ref "IC3") (pin "AJ19") (pinfunction "GND_CP_SXR_AJ19") (pintype "passive"))
      (node (ref "IC3") (pin "AK20") (pinfunction "GND_DIV_SXR_AK20") (pintype "passive"))
      (node (ref "IC3") (pin "AL23") (pinfunction "GND_VCO_SXR_AL23") (pintype "passive"))
      (node (ref "IC3") (pin "AM22") (pinfunction "DGND_SXR_AM22") (pintype "passive"))
      (node (ref "IC3") (pin "AN25") (pinfunction "GND_RXBUF_AN25") (pintype "passive"))
      (node (ref "IC3") (pin "B18") (pinfunction "DGND_CGEN_B18") (pintype "passive"))
      (node (ref "IC3") (pin "B20") (pinfunction "GND_CP_CGEN_B20") (pintype "passive"))
      (node (ref "IC3") (pin "C23") (pinfunction "GND_DIG_C23") (pintype "passive"))
      (node (ref "IC3") (pin "C7") (pinfunction "GND_TLOBUF_TRF_C7") (pintype "passive"))
      (node (ref "IC3") (pin "D20") (pinfunction "GND_DIV_CGEN_D20") (pintype "passive"))
      (node (ref "IC3") (pin "E25") (pinfunction "GND_SPI_BUF_E25") (pintype "passive"))
      (node (ref "IC3") (pin "F6") (pinfunction "GND_TXBUF_F6") (pintype "passive"))
      (node (ref "IC3") (pin "G31") (pinfunction "DIGPRGND2_G31") (pintype "passive"))
      (node (ref "IC3") (pin "GND") (pinfunction "EP_GND") (pintype "passive"))
      (node (ref "IC3") (pin "H2") (pinfunction "GND_VCO_SXT_H2") (pintype "passive"))
      (node (ref "IC3") (pin "J33") (pinfunction "DIGPRGND1_J33") (pintype "passive"))
      (node (ref "IC3") (pin "K4") (pinfunction "GND_CP_SXT_K4") (pintype "passive"))
      (node (ref "IC3") (pin "L3") (pinfunction "GND_DIV_SXT_L3") (pintype "passive"))
      (node (ref "IC3") (pin "N3") (pinfunction "DGND_SXT_N3") (pintype "passive"))
      (node (ref "IC3") (pin "T30") (pinfunction "DIGPRGND1,2_T30") (pintype "passive"))
      (node (ref "IC3") (pin "W29") (pinfunction "DIGPRGND1_W29") (pintype "passive"))
      (node (ref "IC3") (pin "Y30") (pinfunction "DIGPRGND2_Y30") (pintype "passive"))
    )
    (net (code "2") (name "Net-(C141-Pad1)") (class "Default")
      (node (ref "C141") (pin "1") (pinfunction "1_1") (pintype "passive"))
      (node (ref "C142") (pin "1") (pinfunction "1_1") (pintype "passive"))
      (node (ref "C148") (pin "1") (pinfunction "1_1") (pintype "passive"))
      (node (ref "C149") (pin "1") (pinfunction "1_1") (pintype "passive"))
      (node (ref "C150") (pin "1") (pinfunction "1_1") (pintype "passive"))
      (node (ref "C151") (pin "1") (pinfunction "1_1") (pintype "passive"))
      (node (ref "C152") (pin "1") (pinfunction "1_1") (pintype "passive"))
      (node (ref "C153") (pin "1") (pinfunction "1_1") (pintype "passive"))
      (node (ref "IC3") (pin "AA29") (pinfunction "DIGPRVDD1_AA29") (pintype "power_in"))
      (node (ref "IC3") (pin "AE29") (pinfunction "DIGPRVDD1_AE29") (pintype "power_in"))
      (node (ref "IC3") (pin "L33") (pinfunction "DIGPRVDD1_L33") (pintype "power_in"))
      (node (ref "IC3") (pin "R31") (pinfunction "DIGPRVDD1_R31") (pintype "power_in"))
      (node (ref "R86") (pin "2") (pinfunction "2_2") (pintype "passive"))
      (node (ref "R87") (pin "2") (pinfunction "2_2") (pintype "passive"))
    )
    (net (code "3") (name "Net-(C169-Pad2)") (class "Default")
      (node (ref "C169") (pin "2") (pinfunction "2_2") (pintype "passive"))
      (node (ref "FR45") (pin "1") (pinfunction "1_1") (pintype "passive"))
      (node (ref "R88") (pin "2") (pinfunction "2_2") (pintype "passive"))
      (node (ref "R89") (pin "2") (pinfunction "2_2") (pintype "passive"))
    )
    (net (code "4") (name "Net-(C180-Pad1)") (class "Default")
      (node (ref "C180") (pin "1") (pinfunction "1_1") (pintype "passive"))
      (node (ref "C181") (pin "1") (pinfunction "1_1") (pintype "passive"))
      (node (ref "IC3") (pin "H32") (pinfunction "DIGPRVDD2_H32") (pintype "power_in"))
      (node (ref "R94") (pin "2") (pinfunction "2_2") (pintype "passive"))
    )
    (net (code "5") (name "Net-(C182-Pad1)") (class "Default")
      (node (ref "C182") (pin "1") (pinfunction "1_1") (pintype "passive"))
      (node (ref "C183") (pin "1") (pinfunction "1_1") (pintype "passive"))
      (node (ref "IC3") (pin "T32") (pinfunction "DIGPRVDD2_T32") (pintype "power_in"))
      (node (ref "R93") (pin "2") (pinfunction "2_2") (pintype "passive"))
    )
    (net (code "6") (name "Net-(C184-Pad1)") (class "Default")
      (node (ref "C184") (pin "1") (pinfunction "1_1") (pintype "passive"))
      (node (ref "C185") (pin "1") (pinfunction "1_1") (pintype "passive"))
      (node (ref "IC3") (pin "W33") (pinfunction "DIGPRVDD2_W33") (pintype "power_in"))
      (node (ref "R92") (pin "2") (pinfunction "2_2") (pintype "passive"))
    )
    (net (code "7") (name "Net-(C186-Pad1)") (class "Default")
      (node (ref "C186") (pin "1") (pinfunction "1_1") (pintype "passive"))
      (node (ref "C187") (pin "1") (pinfunction "1_1") (pintype "passive"))
      (node (ref "IC3") (pin "AH30") (pinfunction "DIGPRVDD2_AH30") (pintype "power_in"))
      (node (ref "R91") (pin "2") (pinfunction "2_2") (pintype "passive"))
    )
    (net (code "8") (name "Net-(C198-Pad1)") (class "Default")
      (node (ref "C198") (pin "1") (pinfunction "1_1") (pintype "passive"))
      (node (ref "FR66") (pin "2") (pinfunction "2_2") (pintype "passive"))
      (node (ref "R97") (pin "2") (pinfunction "2_2") (pintype "passive"))
    )
    (net (code "9") (name "Net-(C199-Pad1)") (class "Default")
      (node (ref "C199") (pin "1") (pinfunction "1_1") (pintype "passive"))
      (node (ref "FR65") (pin "1") (pinfunction "1_1") (pintype "passive"))
      (node (ref "R96") (pin "1") (pinfunction "1_1") (pintype "passive"))
    )
    (net (code "10") (name "Net-(IC3E-DIGPRPOC)") (class "Default")
      (node (ref "C178") (pin "1") (pinfunction "1_1") (pintype "passive"))
      (node (ref "C179") (pin "1") (pinfunction "1_1") (pintype "passive"))
      (node (ref "IC3") (pin "W31") (pinfunction "DIGPRPOC_W31") (pintype "power_in"))
      (node (ref "R95") (pin "2") (pinfunction "2_2") (pintype "passive"))
    )
    (net (code "11") (name "Net-(IC3E-VDD18_BIAS)") (class "Default")
      (node (ref "C191") (pin "1") (pinfunction "1_1") (pintype "passive"))
      (node (ref "FR62") (pin "1") (pinfunction "1_1") (pintype "passive"))
      (node (ref "IC3") (pin "E17") (pinfunction "VDD18_BIAS_E17") (pintype "power_in"))
    )
    (net (code "12") (name "Net-(IC3E-VDD18_DIG)") (class "Default")
      (node (ref "C176") (pin "1") (pinfunction "1_1") (pintype "passive"))
      (node (ref "IC3") (pin "D24") (pinfunction "VDD18_DIG_D24") (pintype "power_in"))
      (node (ref "R90") (pin "1") (pinfunction "1_1") (pintype "passive"))
    )
    (net (code "13") (name "Net-(IC3E-VDD18_LDO_RX)") (class "Default")
      (node (ref "C194") (pin "1") (pinfunction "1_1") (pintype "passive"))
      (node (ref "FR59") (pin "2") (pinfunction "2_2") (pintype "passive"))
      (node (ref "IC3") (pin "AE3") (pinfunction "VDD18_TIA_RFE_AE3") (pintype "power_in"))
      (node (ref "IC3") (pin "AF4") (pinfunction "VDD18_LDO_RX_AF4") (pintype "power_in"))
    )
    (net (code "14") (name "Net-(IC3E-VDD18_LDO_TX)") (class "Default")
      (node (ref "C195") (pin "1") (pinfunction "1_1") (pintype "passive"))
      (node (ref "FR58") (pin "2") (pinfunction "2_2") (pintype "passive"))
      (node (ref "IC3") (pin "N1") (pinfunction "VDD18_LDO_TX_N1") (pintype "power_in"))
    )
    (net (code "15") (name "Net-(IC3E-VDD18_RXBUF)") (class "Default")
      (node (ref "C196") (pin "1") (pinfunction "1_1") (pintype "passive"))
      (node (ref "FR66") (pin "1") (pinfunction "1_1") (pintype "passive"))
      (node (ref "IC3") (pin "AM26") (pinfunction "VDD18_RXBUF_AM26") (pintype "power_in"))
    )
    (net (code "16") (name "Net-(IC3E-VDD18_SXR)") (class "Default")
      (node (ref "C193") (pin "1") (pinfunction "1_1") (pintype "passive"))
      (node (ref "FR60") (pin "1") (pinfunction "1_1") (pintype "passive"))
      (node (ref "IC3") (pin "AM18") (pinfunction "VDD18_SXR_AM18") (pintype "power_in"))
    )
    (net (code "17") (name "Net-(IC3E-VDD18_TRF)") (class "Default")
      (node (ref "C190") (pin "1") (pinfunction "1_1") (pintype "passive"))
      (node (ref "FR63") (pin "1") (pinfunction "1_1") (pintype "passive"))
      (node (ref "IC3") (pin "D16") (pinfunction "VDD18_TRF_D16") (pintype "power_in"))
    )
    (net (code "18") (name "Net-(IC3E-VDD18_TXBUF)") (class "Default")
      (node (ref "C197") (pin "1") (pinfunction "1_1") (pintype "passive"))
      (node (ref "FR65") (pin "2") (pinfunction "2_2") (pintype "passive"))
      (node (ref "IC3") (pin "H6") (pinfunction "VDD18_TXBUF_H6") (pintype "power_in"))
    )
    (net (code "19") (name "Net-(IC3E-VDD18_VCO_CGEN)") (class "Default")
      (node (ref "C189") (pin "1") (pinfunction "1_1") (pintype "passive"))
      (node (ref "FR64") (pin "1") (pinfunction "1_1") (pintype "passive"))
      (node (ref "IC3") (pin "E21") (pinfunction "VDD18_VCO_CGEN_E21") (pintype "power_in"))
    )
    (net (code "20") (name "Net-(IC3E-VDD18_VCO_SXR)") (class "Default")
      (node (ref "C192") (pin "1") (pinfunction "1_1") (pintype "passive"))
      (node (ref "FR61") (pin "1") (pinfunction "1_1") (pintype "passive"))
      (node (ref "IC3") (pin "AK22") (pinfunction "VDD18_VCO_SXR_AK22") (pintype "power_in"))
    )
    (net (code "21") (name "Net-(IC3E-VDD18_VCO_SXT)") (class "Default")
      (node (ref "C188") (pin "1") (pinfunction "1_1") (pintype "passive"))
      (node (ref "FR57") (pin "1") (pinfunction "1_1") (pintype "passive"))
      (node (ref "IC3") (pin "G3") (pinfunction "VDD18_VCO_SXT_G3") (pintype "power_in"))
    )
    (net (code "22") (name "Net-(IC3F-DVDD_CGEN)") (class "Default")
      (node (ref "C143") (pin "1") (pinfunction "1_1") (pintype "passive"))
      (node (ref "C144") (pin "1") (pinfunction "1_1") (pintype "passive"))
      (node (ref "C145") (pin "1") (pinfunction "1_1") (pintype "passive"))
      (node (ref "FR36") (pin "1") (pinfunction "1_1") (pintype "passive"))
      (node (ref "IC3") (pin "A17") (pinfunction "DVDD_CGEN_A17") (pintype "power_in"))
      (node (ref "IC3") (pin "C25") (pinfunction "VDD12_DIG_C25") (pintype "power_in"))
      (node (ref "IC3") (pin "F24") (pinfunction "VDD_SPI_BUF_F24") (pintype "power_in"))
    )
    (net (code "23") (name "Net-(IC3F-DVDD_SXR)") (class "Default")
      (node (ref "C147") (pin "1") (pinfunction "1_1") (pintype "passive"))
      (node (ref "FR34") (pin "1") (pinfunction "1_1") (pintype "passive"))
      (node (ref "IC3") (pin "AL21") (pinfunction "DVDD_SXR_AL21") (pintype "power_in"))
    )
    (net (code "24") (name "Net-(IC3F-DVDD_SXT)") (class "Default")
      (node (ref "C146") (pin "2") (pinfunction "2_2") (pintype "passive"))
      (node (ref "FR35") (pin "1") (pinfunction "1_1") (pintype "passive"))
      (node (ref "IC3") (pin "M4") (pinfunction "DVDD_SXT_M4") (pintype "power_in"))
    )
    (net (code "25") (name "Net-(IC3F-VDD12O_VCO_SXT)") (class "Default")
      (node (ref "C168") (pin "2") (pinfunction "2_2") (pintype "passive"))
      (node (ref "FR37") (pin "1") (pinfunction "1_1") (pintype "passive"))
      (node (ref "IC3") (pin "J5") (pinfunction "VDD12O_VCO_SXT_J5") (pintype "power_in"))
      (node (ref "IC3") (pin "K6") (pinfunction "VDD12_VCO_SXT_K6") (pintype "power_in"))
    )
    (net (code "26") (name "Net-(IC3F-VDD12_LNA_RFE)") (class "Default")
      (node (ref "C165") (pin "1") (pinfunction "1_1") (pintype "passive"))
      (node (ref "FR41") (pin "1") (pinfunction "1_1") (pintype "passive"))
      (node (ref "IC3") (pin "AG5") (pinfunction "VDD12_LNA_RFE_AG5") (pintype "power_in"))
    )
    (net (code "27") (name "Net-(IC3F-VDD12_RXBUF)") (class "Default")
      (node (ref "C161") (pin "1") (pinfunction "1_1") (pintype "passive"))
      (node (ref "IC3") (pin "AP26") (pinfunction "VDD12_RXBUF_AP26") (pintype "power_in"))
      (node (ref "R89") (pin "1") (pinfunction "1_1") (pintype "passive"))
    )
    (net (code "28") (name "Net-(IC3F-VDD12_TIA_RFE)") (class "Default")
      (node (ref "C166") (pin "2") (pinfunction "2_2") (pintype "passive"))
      (node (ref "FR40") (pin "1") (pinfunction "1_1") (pintype "passive"))
      (node (ref "IC3") (pin "AD6") (pinfunction "VDD12_TIA_RFE_AD6") (pintype "power_in"))
    )
    (net (code "29") (name "Net-(IC3F-VDD12_TXBUF)") (class "Default")
      (node (ref "C154") (pin "1") (pinfunction "1_1") (pintype "passive"))
      (node (ref "IC3") (pin "G5") (pinfunction "VDD12_TXBUF_G5") (pintype "power_in"))
      (node (ref "R88") (pin "1") (pinfunction "1_1") (pintype "passive"))
    )
    (net (code "30") (name "Net-(IC3F-VDD12_VCO_SXR)") (class "Default")
      (node (ref "C162") (pin "1") (pinfunction "1_1") (pintype "passive"))
      (node (ref "FR44") (pin "1") (pinfunction "1_1") (pintype "passive"))
      (node (ref "IC3") (pin "AN23") (pinfunction "VDD12_VCO_SXR_AN23") (pintype "power_in"))
    )
    (net (code "31") (name "Net-(IC3F-VDD14_LNA_RFE)") (class "Default")
      (node (ref "C172") (pin "1") (pinfunction "1_1") (pintype "passive"))
      (node (ref "FR55") (pin "1") (pinfunction "1_1") (pintype "passive"))
      (node (ref "IC3") (pin "AF6") (pinfunction "VDD14_LNA_RFE_AF6") (pintype "power_in"))
    )
    (net (code "32") (name "Net-(IC3F-VDD14_RBB)") (class "Default")
      (node (ref "C174") (pin "1") (pinfunction "1_1") (pintype "passive"))
      (node (ref "FR53") (pin "1") (pinfunction "1_1") (pintype "passive"))
      (node (ref "IC3") (pin "AD4") (pinfunction "VDD14_RBB_AD4") (pintype "power_in"))
    )
    (net (code "33") (name "Net-(IC3F-VDD14_TIA_RFE)") (class "Default")
      (node (ref "C173") (pin "1") (pinfunction "1_1") (pintype "passive"))
      (node (ref "FR54") (pin "1") (pinfunction "1_1") (pintype "passive"))
      (node (ref "IC3") (pin "AF2") (pinfunction "VDD14_TIA_RFE_AF2") (pintype "power_in"))
    )
    (net (code "34") (name "Net-(IC3F-VDD14_VCO_CGEN)") (class "Default")
      (node (ref "C171") (pin "1") (pinfunction "1_1") (pintype "passive"))
      (node (ref "FR56") (pin "1") (pinfunction "1_1") (pintype "passive"))
      (node (ref "IC3") (pin "C21") (pinfunction "VDD14_VCO_CGEN_C21") (pintype "power_in"))
    )
    (net (code "35") (name "Net-(IC3F-VDDO_DIV_SXT)") (class "Default")
      (node (ref "C170") (pin "1") (pinfunction "1_1") (pintype "passive"))
      (node (ref "FR51") (pin "1") (pinfunction "1_1") (pintype "passive"))
      (node (ref "IC3") (pin "K2") (pinfunction "VDDO_DIV_SXT_K2") (pintype "power_in"))
      (node (ref "IC3") (pin "L5") (pinfunction "VDD_DIV_SXT_L5") (pintype "power_in"))
    )
    (net (code "36") (name "Net-(IC3F-VDDO_TLOBUF_TRF)") (class "Default")
      (node (ref "C156") (pin "1") (pinfunction "1_1") (pintype "passive"))
      (node (ref "FR50") (pin "1") (pinfunction "1_1") (pintype "passive"))
      (node (ref "IC3") (pin "D6") (pinfunction "VDDO_TLOBUF_TRF_D6") (pintype "power_in"))
      (node (ref "IC3") (pin "F8") (pinfunction "VDD_TLOBUF_TRF_F8") (pintype "power_in"))
    )
    (net (code "37") (name "Net-(IC3F-VDD_AFE)") (class "Default")
      (node (ref "C160") (pin "1") (pinfunction "1_1") (pintype "passive"))
      (node (ref "FR46") (pin "1") (pinfunction "1_1") (pintype "passive"))
      (node (ref "IC3") (pin "AJ25") (pinfunction "VDD_AFE_AJ25") (pintype "power_in"))
    )
    (net (code "38") (name "Net-(IC3F-VDD_CP_CGEN)") (class "Default")
      (node (ref "C159") (pin "2") (pinfunction "2_2") (pintype "passive"))
      (node (ref "FR47") (pin "1") (pinfunction "1_1") (pintype "passive"))
      (node (ref "IC3") (pin "F20") (pinfunction "VDD_CP_CGEN_F20") (pintype "power_in"))
    )
    (net (code "39") (name "Net-(IC3F-VDD_CP_SXR)") (class "Default")
      (node (ref "C164") (pin "1") (pinfunction "1_1") (pintype "passive"))
      (node (ref "FR42") (pin "1") (pinfunction "1_1") (pintype "passive"))
      (node (ref "IC3") (pin "AL19") (pinfunction "VDD_CP_SXR_AL19") (pintype "power_in"))
    )
    (net (code "40") (name "Net-(IC3F-VDD_CP_SXT)") (class "Default")
      (node (ref "C167") (pin "1") (pinfunction "1_1") (pintype "passive"))
      (node (ref "FR38") (pin "1") (pinfunction "1_1") (pintype "passive"))
      (node (ref "IC3") (pin "J3") (pinfunction "VDD_CP_SXT_J3") (pintype "power_in"))
    )
    (net (code "41") (name "Net-(IC3F-VDD_DIV_CGEN)") (class "Default")
      (node (ref "C158") (pin "1") (pinfunction "1_1") (pintype "passive"))
      (node (ref "FR48") (pin "1") (pinfunction "1_1") (pintype "passive"))
      (node (ref "IC3") (pin "E19") (pinfunction "VDD_DIV_CGEN_E19") (pintype "power_in"))
    )
    (net (code "42") (name "Net-(IC3F-VDD_DIV_SXR)") (class "Default")
      (node (ref "C163") (pin "1") (pinfunction "1_1") (pintype "passive"))
      (node (ref "FR43") (pin "1") (pinfunction "1_1") (pintype "passive"))
      (node (ref "IC3") (pin "AM20") (pinfunction "VDD_DIV_SXR_AM20") (pintype "power_in"))
    )
    (net (code "43") (name "Net-(IC3F-VDD_MXLOBUF_RFE)") (class "Default")
      (node (ref "C175") (pin "1") (pinfunction "1_1") (pintype "passive"))
      (node (ref "FR52") (pin "1") (pinfunction "1_1") (pintype "passive"))
      (node (ref "IC3") (pin "AN17") (pinfunction "VDD_MXLOBUF_RFE_AN17") (pintype "power_in"))
    )
    (net (code "44") (name "Net-(IC3F-VDD_TBB)") (class "Default")
      (node (ref "C155") (pin "1") (pinfunction "1_1") (pintype "passive"))
      (node (ref "FR39") (pin "1") (pinfunction "1_1") (pintype "passive"))
      (node (ref "IC3") (pin "P4") (pinfunction "VDD_TBB_P4") (pintype "power_in"))
    )
    (net (code "45") (name "Net-(IC3F-VDD_TPAD_TRF)") (class "Default")
      (node (ref "C157") (pin "1") (pinfunction "1_1") (pintype "passive"))
      (node (ref "FR49") (pin "1") (pinfunction "1_1") (pintype "passive"))
      (node (ref "IC3") (pin "B16") (pinfunction "VDD_TPAD_TRF_B16") (pintype "power_in"))
    )
    (net (code "46") (name "VCC1P4_LMS2") (class "Default")
      (node (ref "FR51") (pin "2") (pinfunction "2_2") (pintype "passive"))
      (node (ref "FR52") (pin "2") (pinfunction "2_2") (pintype "passive"))
      (node (ref "FR53") (pin "2") (pinfunction "2_2") (pintype "passive"))
      (node (ref "FR54") (pin "2") (pinfunction "2_2") (pintype "passive"))
      (node (ref "FR55") (pin "2") (pinfunction "2_2") (pintype "passive"))
      (node (ref "FR56") (pin "2") (pinfunction "2_2") (pintype "passive"))
      (node (ref "R86") (pin "1") (pinfunction "1_1") (pintype "passive"))
    )
    (net (code "47") (name "VCC1P8_LMS2") (class "Default")
      (node (ref "FR57") (pin "2") (pinfunction "2_2") (pintype "passive"))
      (node (ref "FR58") (pin "1") (pinfunction "1_1") (pintype "passive"))
      (node (ref "FR59") (pin "1") (pinfunction "1_1") (pintype "passive"))
      (node (ref "FR60") (pin "2") (pinfunction "2_2") (pintype "passive"))
      (node (ref "FR61") (pin "2") (pinfunction "2_2") (pintype "passive"))
      (node (ref "FR62") (pin "2") (pinfunction "2_2") (pintype "passive"))
      (node (ref "FR63") (pin "2") (pinfunction "2_2") (pintype "passive"))
      (node (ref "FR64") (pin "2") (pinfunction "2_2") (pintype "passive"))
      (node (ref "R90") (pin "2") (pinfunction "2_2") (pintype "passive"))
      (node (ref "R96") (pin "2") (pinfunction "2_2") (pintype "passive"))
      (node (ref "R97") (pin "1") (pinfunction "1_1") (pintype "passive"))
    )
    (net (code "48") (name "VCC1P25_LMS2") (class "Default")
      (node (ref "FR34") (pin "2") (pinfunction "2_2") (pintype "passive"))
      (node (ref "FR35") (pin "2") (pinfunction "2_2") (pintype "passive"))
      (node (ref "FR36") (pin "2") (pinfunction "2_2") (pintype "passive"))
      (node (ref "FR37") (pin "2") (pinfunction "2_2") (pintype "passive"))
      (node (ref "FR38") (pin "2") (pinfunction "2_2") (pintype "passive"))
      (node (ref "FR39") (pin "2") (pinfunction "2_2") (pintype "passive"))
      (node (ref "FR40") (pin "2") (pinfunction "2_2") (pintype "passive"))
      (node (ref "FR41") (pin "2") (pinfunction "2_2") (pintype "passive"))
      (node (ref "FR42") (pin "2") (pinfunction "2_2") (pintype "passive"))
      (node (ref "FR43") (pin "2") (pinfunction "2_2") (pintype "passive"))
      (node (ref "FR44") (pin "2") (pinfunction "2_2") (pintype "passive"))
      (node (ref "FR45") (pin "2") (pinfunction "2_2") (pintype "passive"))
      (node (ref "FR46") (pin "2") (pinfunction "2_2") (pintype "passive"))
      (node (ref "FR47") (pin "2") (pinfunction "2_2") (pintype "passive"))
      (node (ref "FR48") (pin "2") (pinfunction "2_2") (pintype "passive"))
      (node (ref "FR49") (pin "2") (pinfunction "2_2") (pintype "passive"))
      (node (ref "FR50") (pin "2") (pinfunction "2_2") (pintype "passive"))
      (node (ref "R87") (pin "1") (pinfunction "1_1") (pintype "passive"))
    )
    (net (code "49") (name "VDIO_LMS") (class "Default")
      (node (ref "C177") (pin "2") (pinfunction "2_2") (pintype "passive"))
      (node (ref "R91") (pin "1") (pinfunction "1_1") (pintype "passive"))
      (node (ref "R92") (pin "1") (pinfunction "1_1") (pintype "passive"))
      (node (ref "R93") (pin "1") (pinfunction "1_1") (pintype "passive"))
      (node (ref "R94") (pin "1") (pinfunction "1_1") (pintype "passive"))
      (node (ref "R95") (pin "1") (pinfunction "1_1") (pintype "passive"))
    )
  )
)
